# Transmitter.net
KiCad netlist of a schematic drawn in EAGLE
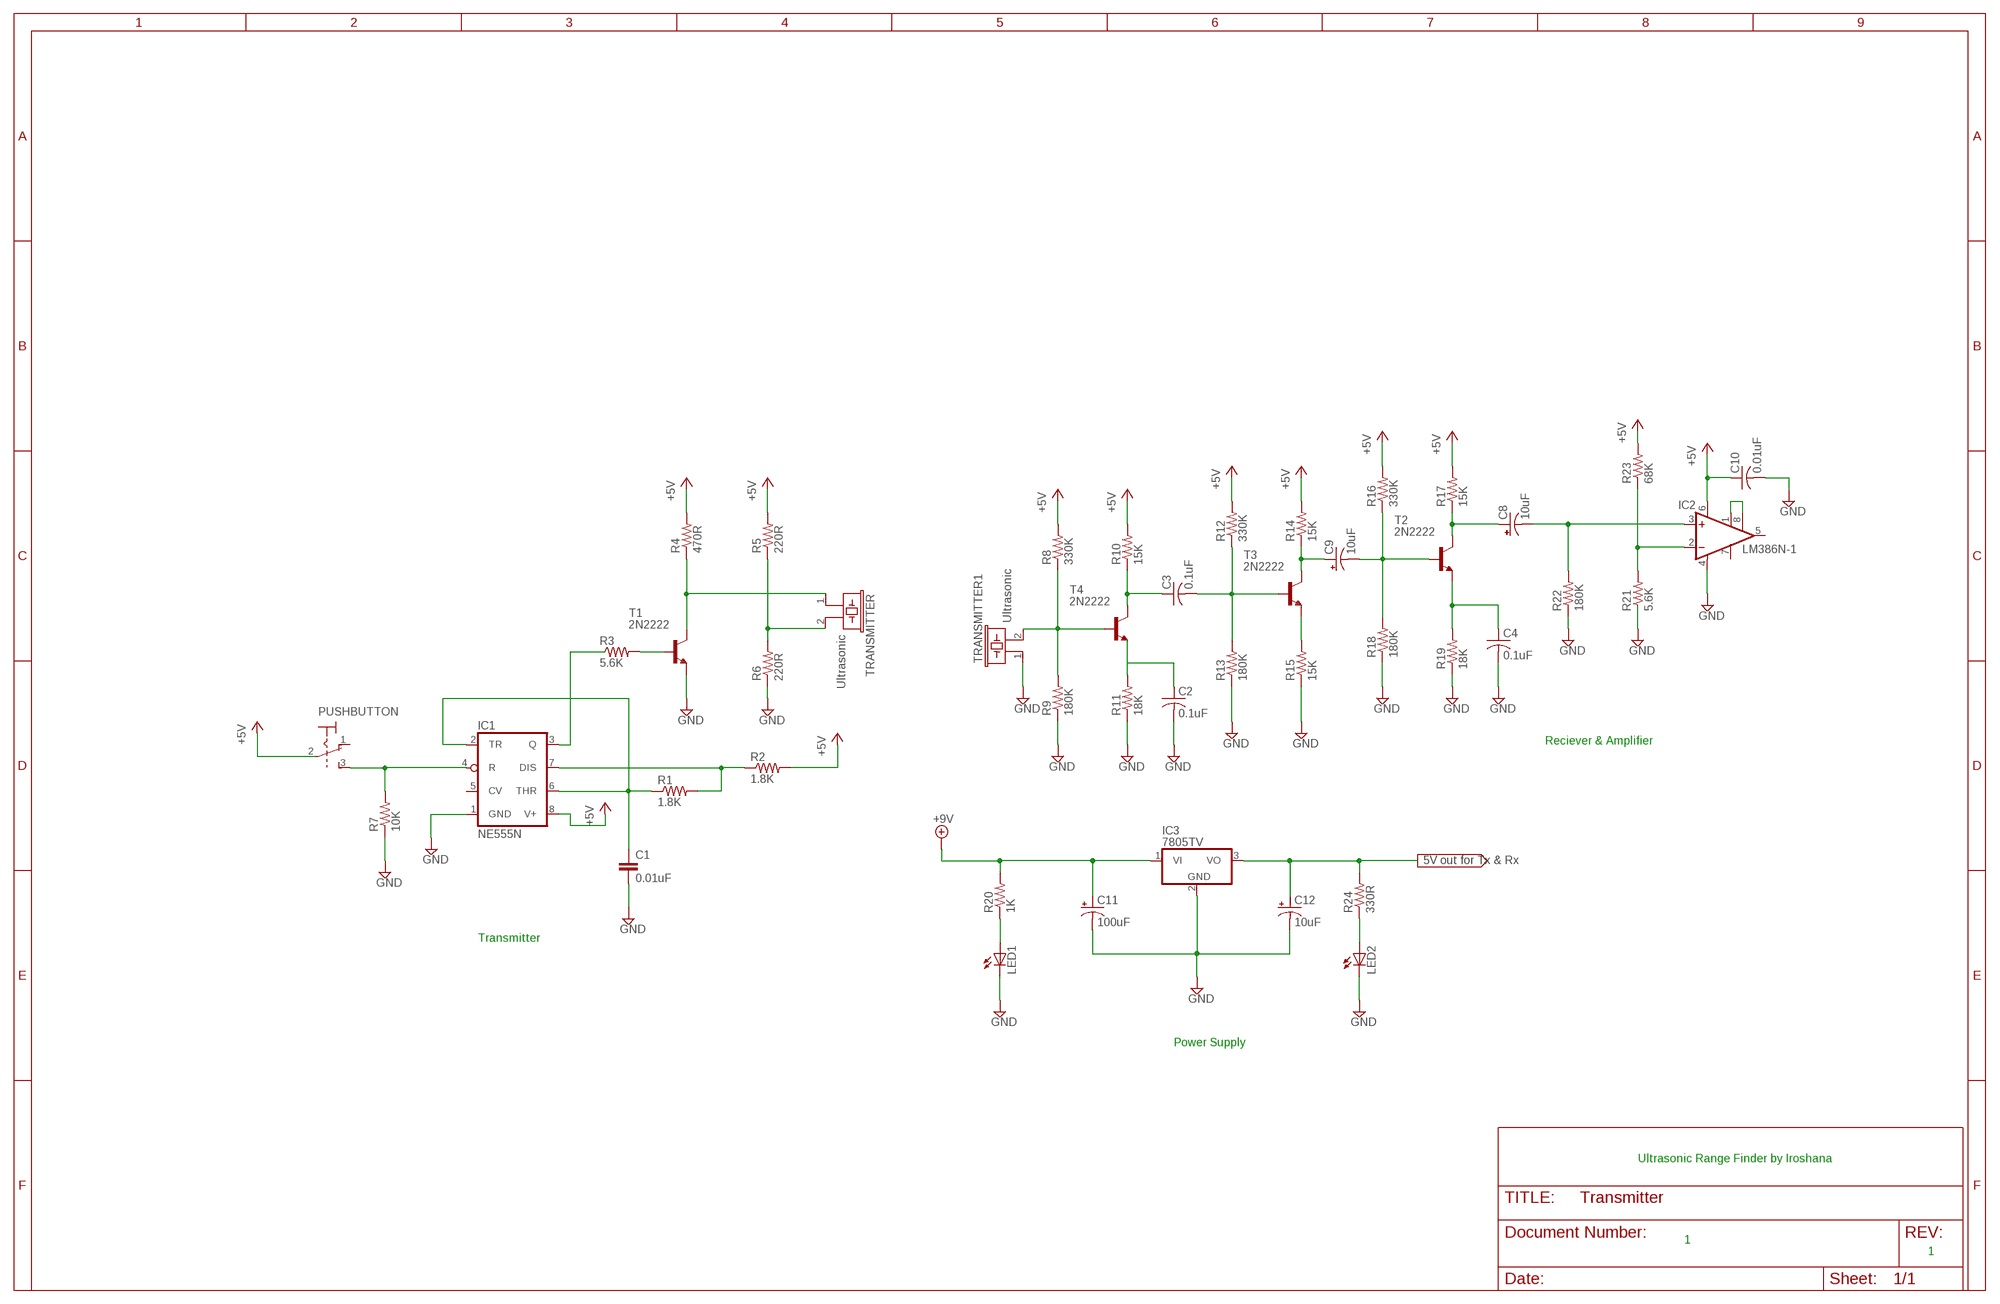
[diagram p0: schematic, sheet 1]

(export (version "E")
  (design (tool "Eeschema 10.0.6"))
  (components
    (comp (ref "C1")
      (value "0.01uF")
      (footprint "eagle-import:C2.5-2")
      (libsource (lib "eagle-import") (part "C2.5/2"))
    )
    (comp (ref "C2")
      (value "0.1uF")
      (footprint "eagle-import:C025-025X050")
      (libsource (lib "eagle-import") (part "C-US025-025X050"))
    )
    (comp (ref "C3")
      (value "0.1uF")
      (footprint "eagle-import:C025-025X050")
      (libsource (lib "eagle-import") (part "C-US025-025X050"))
    )
    (comp (ref "C4")
      (value "0.1uF")
      (footprint "eagle-import:C025-025X050")
      (libsource (lib "eagle-import") (part "C-US025-025X050"))
    )
    (comp (ref "C8")
      (value "10uF")
      (footprint "eagle-import:E2,5-6")
      (libsource (lib "eagle-import") (part "CPOL-USE2.5-6"))
    )
    (comp (ref "C9")
      (value "10uF")
      (footprint "eagle-import:E2,5-6")
      (libsource (lib "eagle-import") (part "CPOL-USE2.5-6"))
    )
    (comp (ref "C10")
      (value "0.01uF")
      (footprint "eagle-import:C025-025X050")
      (libsource (lib "eagle-import") (part "C-US025-025X050"))
    )
    (comp (ref "C11")
      (value "100uF")
      (footprint "eagle-import:E2,5-6")
      (libsource (lib "eagle-import") (part "CPOL-USE2.5-6"))
    )
    (comp (ref "C12")
      (value "10uF")
      (footprint "eagle-import:E2,5-6")
      (libsource (lib "eagle-import") (part "CPOL-USE2.5-6"))
    )
    (comp (ref "IC1")
      (value "NE555N")
      (footprint "eagle-import:DIL08-ROUND")
      (libsource (lib "eagle-import") (part "555NNE"))
    )
    (comp (ref "IC2")
      (value "LM386N-1")
      (footprint "eagle-import:DIL08")
      (libsource (lib "eagle-import") (part "LM386?-N1"))
    )
    (comp (ref "IC3")
      (value "7805TV")
      (footprint "eagle-import:TO220V")
      (libsource (lib "eagle-import") (part "78TV05"))
    )
    (comp (ref "LED1")
      (value "LED5MM")
      (footprint "eagle-import:LED5MM")
      (libsource (lib "eagle-import") (part "LED5MM"))
    )
    (comp (ref "LED2")
      (value "LED5MM")
      (footprint "eagle-import:LED5MM")
      (libsource (lib "eagle-import") (part "LED5MM"))
    )
    (comp (ref "PUSHBUTTON")
      (value "M9040P2")
      (footprint "eagle-import:M9040P2")
      (libsource (lib "eagle-import") (part "M9040P2"))
    )
    (comp (ref "R1")
      (value "1.8K")
      (footprint "eagle-import:0207_10")
      (libsource (lib "eagle-import") (part "resistor_R-US_0207/10"))
    )
    (comp (ref "R2")
      (value "1.8K")
      (footprint "eagle-import:0207_10")
      (libsource (lib "eagle-import") (part "resistor_R-US_0207/10"))
    )
    (comp (ref "R3")
      (value "5.6K")
      (footprint "eagle-import:0207_10")
      (libsource (lib "eagle-import") (part "resistor_R-US_0207/10"))
    )
    (comp (ref "R4")
      (value "470R")
      (footprint "eagle-import:0207_10")
      (libsource (lib "eagle-import") (part "resistor_R-US_0207/10"))
    )
    (comp (ref "R5")
      (value "220R")
      (footprint "eagle-import:0207_10")
      (libsource (lib "eagle-import") (part "resistor_R-US_0207/10"))
    )
    (comp (ref "R6")
      (value "220R")
      (footprint "eagle-import:0207_10")
      (libsource (lib "eagle-import") (part "resistor_R-US_0207/10"))
    )
    (comp (ref "R7")
      (value "10K")
      (footprint "eagle-import:0207_10")
      (libsource (lib "eagle-import") (part "resistor_R-US_0207/10"))
    )
    (comp (ref "R8")
      (value "330K")
      (footprint "eagle-import:0207_10")
      (libsource (lib "eagle-import") (part "R-US_0207/10"))
    )
    (comp (ref "R9")
      (value "180K")
      (footprint "eagle-import:0207_10")
      (libsource (lib "eagle-import") (part "R-US_0207/10"))
    )
    (comp (ref "R10")
      (value "15K")
      (footprint "eagle-import:0207_10")
      (libsource (lib "eagle-import") (part "R-US_0207/10"))
    )
    (comp (ref "R11")
      (value "18K")
      (footprint "eagle-import:0207_10")
      (libsource (lib "eagle-import") (part "R-US_0207/10"))
    )
    (comp (ref "R12")
      (value "330K")
      (footprint "eagle-import:0207_10")
      (libsource (lib "eagle-import") (part "R-US_0207/10"))
    )
    (comp (ref "R13")
      (value "180K")
      (footprint "eagle-import:0207_10")
      (libsource (lib "eagle-import") (part "R-US_0207/10"))
    )
    (comp (ref "R14")
      (value "15K")
      (footprint "eagle-import:0207_10")
      (libsource (lib "eagle-import") (part "R-US_0207/10"))
    )
    (comp (ref "R15")
      (value "15K")
      (footprint "eagle-import:0207_10")
      (libsource (lib "eagle-import") (part "R-US_0207/10"))
    )
    (comp (ref "R16")
      (value "330K")
      (footprint "eagle-import:0207_10")
      (libsource (lib "eagle-import") (part "R-US_0207/10"))
    )
    (comp (ref "R17")
      (value "15K")
      (footprint "eagle-import:0207_10")
      (libsource (lib "eagle-import") (part "R-US_0207/10"))
    )
    (comp (ref "R18")
      (value "180K")
      (footprint "eagle-import:0207_10")
      (libsource (lib "eagle-import") (part "R-US_0207/10"))
    )
    (comp (ref "R19")
      (value "18K")
      (footprint "eagle-import:0207_10")
      (libsource (lib "eagle-import") (part "R-US_0207/10"))
    )
    (comp (ref "R20")
      (value "1K")
      (footprint "eagle-import:0207_10")
      (libsource (lib "eagle-import") (part "R-US_0207/10"))
    )
    (comp (ref "R21")
      (value "5.6K")
      (footprint "eagle-import:0207_10")
      (libsource (lib "eagle-import") (part "R-US_0207/10"))
    )
    (comp (ref "R22")
      (value "180K")
      (footprint "eagle-import:0207_10")
      (libsource (lib "eagle-import") (part "R-US_0207/10"))
    )
    (comp (ref "R23")
      (value "68K")
      (footprint "eagle-import:0207_10")
      (libsource (lib "eagle-import") (part "R-US_0207/10"))
    )
    (comp (ref "R24")
      (value "330R")
      (footprint "eagle-import:0207_10")
      (libsource (lib "eagle-import") (part "R-US_0207/10"))
    )
    (comp (ref "T1")
      (value "2N2222")
      (footprint "eagle-import:TO92-EBC-OVAL")
      (libsource (lib "eagle-import") (part "2N2222"))
    )
    (comp (ref "T2")
      (value "2N2222")
      (footprint "eagle-import:TO92-EBC-OVAL")
      (libsource (lib "eagle-import") (part "2N2222"))
    )
    (comp (ref "T3")
      (value "2N2222")
      (footprint "eagle-import:TO92-EBC-OVAL")
      (libsource (lib "eagle-import") (part "2N2222"))
    )
    (comp (ref "T4")
      (value "2N2222")
      (footprint "eagle-import:TO92-EBC-OVAL")
      (libsource (lib "eagle-import") (part "2N2222"))
    )
    (comp (ref "TRANSMITTER")
      (value "Ultrasonic")
      (footprint "eagle-import:EFBRD22C41")
      (libsource (lib "eagle-import") (part "EFB?RD22C41"))
    )
    (comp (ref "TRANSMITTER1")
      (value "Ultrasonic")
      (footprint "eagle-import:EFBRD22C41")
      (libsource (lib "eagle-import") (part "EFB?RD22C41"))
    )
  )
  (nets
    (net (code "1") (name "+5V") (class "Default")
      (node (ref "C10") (pin "1") (pinfunction "1_1") (pintype "passive"))
      (node (ref "IC1") (pin "8") (pinfunction "V+_8") (pintype "power_in"))
      (node (ref "IC2") (pin "6") (pinfunction "VS_6") (pintype "power_in"))
      (node (ref "R10") (pin "2") (pinfunction "2_2") (pintype "passive"))
      (node (ref "R12") (pin "2") (pinfunction "2_2") (pintype "passive"))
      (node (ref "R14") (pin "2") (pinfunction "2_2") (pintype "passive"))
      (node (ref "R16") (pin "2") (pinfunction "2_2") (pintype "passive"))
      (node (ref "R17") (pin "2") (pinfunction "2_2") (pintype "passive"))
      (node (ref "R2") (pin "2") (pinfunction "2_2") (pintype "passive"))
      (node (ref "R23") (pin "2") (pinfunction "2_2") (pintype "passive"))
      (node (ref "R4") (pin "2") (pinfunction "2_2") (pintype "passive"))
      (node (ref "R5") (pin "2") (pinfunction "2_2") (pintype "passive"))
      (node (ref "R8") (pin "2") (pinfunction "2_2") (pintype "passive"))
    )
    (net (code "2") (name "+9V") (class "Default")
      (node (ref "C11") (pin "+") (pinfunction "+_+") (pintype "passive"))
      (node (ref "IC3") (pin "1") (pinfunction "VI_1") (pintype "input"))
      (node (ref "R20") (pin "2") (pinfunction "2_2") (pintype "passive"))
    )
    (net (code "3") (name "GND") (class "Default")
      (node (ref "C1") (pin "2") (pinfunction "2_2") (pintype "passive"))
      (node (ref "C10") (pin "2") (pinfunction "2_2") (pintype "passive"))
      (node (ref "C11") (pin "-") (pinfunction "-_-") (pintype "passive"))
      (node (ref "C12") (pin "-") (pinfunction "-_-") (pintype "passive"))
      (node (ref "C2") (pin "2") (pinfunction "2_2") (pintype "passive"))
      (node (ref "C4") (pin "2") (pinfunction "2_2") (pintype "passive"))
      (node (ref "IC1") (pin "1") (pinfunction "GND_1") (pintype "power_in"))
      (node (ref "IC2") (pin "4") (pinfunction "GND_4") (pintype "power_in"))
      (node (ref "IC3") (pin "2") (pinfunction "GND_2") (pintype "passive"))
      (node (ref "LED1") (pin "K") (pinfunction "C_K") (pintype "passive"))
      (node (ref "LED2") (pin "K") (pinfunction "C_K") (pintype "passive"))
      (node (ref "R11") (pin "1") (pinfunction "1_1") (pintype "passive"))
      (node (ref "R13") (pin "1") (pinfunction "1_1") (pintype "passive"))
      (node (ref "R15") (pin "1") (pinfunction "1_1") (pintype "passive"))
      (node (ref "R18") (pin "1") (pinfunction "1_1") (pintype "passive"))
      (node (ref "R19") (pin "1") (pinfunction "1_1") (pintype "passive"))
      (node (ref "R22") (pin "1") (pinfunction "1_1") (pintype "passive"))
      (node (ref "R6") (pin "1") (pinfunction "1_1") (pintype "passive"))
      (node (ref "R7") (pin "1") (pinfunction "1_1") (pintype "passive"))
      (node (ref "R9") (pin "1") (pinfunction "1_1") (pintype "passive"))
      (node (ref "T1") (pin "E") (pinfunction "E_E") (pintype "passive"))
      (node (ref "TRANSMITTER1") (pin "1") (pinfunction "1_1") (pintype "passive"))
    )
    (net (code "4") (name "Net-(C2-Pad1)") (class "Default")
      (node (ref "C2") (pin "1") (pinfunction "1_1") (pintype "passive"))
      (node (ref "R11") (pin "2") (pinfunction "2_2") (pintype "passive"))
    )
    (net (code "5") (name "Net-(C3-Pad1)") (class "Default")
      (node (ref "C3") (pin "1") (pinfunction "1_1") (pintype "passive"))
      (node (ref "R10") (pin "1") (pinfunction "1_1") (pintype "passive"))
      (node (ref "T4") (pin "C") (pinfunction "C_C") (pintype "passive"))
    )
    (net (code "6") (name "Net-(C3-Pad2)") (class "Default")
      (node (ref "C3") (pin "2") (pinfunction "2_2") (pintype "passive"))
      (node (ref "R12") (pin "1") (pinfunction "1_1") (pintype "passive"))
      (node (ref "R13") (pin "2") (pinfunction "2_2") (pintype "passive"))
      (node (ref "T3") (pin "B") (pinfunction "B_B") (pintype "passive"))
    )
    (net (code "7") (name "Net-(C4-Pad1)") (class "Default")
      (node (ref "C4") (pin "1") (pinfunction "1_1") (pintype "passive"))
      (node (ref "R19") (pin "2") (pinfunction "2_2") (pintype "passive"))
      (node (ref "T2") (pin "E") (pinfunction "E_E") (pintype "passive"))
    )
    (net (code "8") (name "Net-(C8-Pad+)") (class "Default")
      (node (ref "C8") (pin "+") (pinfunction "+_+") (pintype "passive"))
      (node (ref "R17") (pin "1") (pinfunction "1_1") (pintype "passive"))
      (node (ref "T2") (pin "C") (pinfunction "C_C") (pintype "passive"))
    )
    (net (code "9") (name "Net-(C9-Pad+)") (class "Default")
      (node (ref "C9") (pin "+") (pinfunction "+_+") (pintype "passive"))
      (node (ref "R14") (pin "1") (pinfunction "1_1") (pintype "passive"))
      (node (ref "T3") (pin "C") (pinfunction "C_C") (pintype "passive"))
    )
    (net (code "10") (name "Net-(C9-Pad-)") (class "Default")
      (node (ref "C9") (pin "-") (pinfunction "-_-") (pintype "passive"))
      (node (ref "R16") (pin "1") (pinfunction "1_1") (pintype "passive"))
      (node (ref "R18") (pin "2") (pinfunction "2_2") (pintype "passive"))
      (node (ref "T2") (pin "B") (pinfunction "B_B") (pintype "passive"))
    )
    (net (code "11") (name "Net-(IC1-DIS)") (class "Default")
      (node (ref "IC1") (pin "7") (pinfunction "DIS_7") (pintype "input"))
      (node (ref "R1") (pin "2") (pinfunction "2_2") (pintype "passive"))
      (node (ref "R2") (pin "1") (pinfunction "1_1") (pintype "passive"))
    )
    (net (code "12") (name "Net-(IC1-R)") (class "Default")
      (node (ref "IC1") (pin "4") (pinfunction "R_4") (pintype "input"))
      (node (ref "PUSHBUTTON") (pin "3") (pinfunction "S_3") (pintype "passive"))
      (node (ref "R7") (pin "2") (pinfunction "2_2") (pintype "passive"))
    )
    (net (code "13") (name "Net-(IC1-THR)") (class "Default")
      (node (ref "C1") (pin "1") (pinfunction "1_1") (pintype "passive"))
      (node (ref "IC1") (pin "2") (pinfunction "TR_2") (pintype "input"))
      (node (ref "IC1") (pin "6") (pinfunction "THR_6") (pintype "input"))
      (node (ref "R1") (pin "1") (pinfunction "1_1") (pintype "passive"))
    )
    (net (code "14") (name "Net-(IC2-+IN)") (class "Default")
      (node (ref "C8") (pin "-") (pinfunction "-_-") (pintype "passive"))
      (node (ref "IC2") (pin "3") (pinfunction "+IN_3") (pintype "input"))
      (node (ref "R22") (pin "2") (pinfunction "2_2") (pintype "passive"))
    )
    (net (code "15") (name "Net-(IC2--IN)") (class "Default")
      (node (ref "IC2") (pin "2") (pinfunction "-IN_2") (pintype "input"))
      (node (ref "R21") (pin "2") (pinfunction "2_2") (pintype "passive"))
      (node (ref "R23") (pin "1") (pinfunction "1_1") (pintype "passive"))
    )
    (net (code "16") (name "Net-(IC2-GAIN-Pad1)") (class "Default")
      (node (ref "IC2") (pin "1") (pinfunction "GAIN_1") (pintype "passive"))
      (node (ref "IC2") (pin "8") (pinfunction "GAIN_8") (pintype "passive"))
    )
    (net (code "17") (name "Net-(IC3-VO)") (class "Default")
      (node (ref "C12") (pin "+") (pinfunction "+_+") (pintype "passive"))
      (node (ref "IC3") (pin "3") (pinfunction "VO_3") (pintype "passive"))
      (node (ref "R24") (pin "2") (pinfunction "2_2") (pintype "passive"))
    )
    (net (code "18") (name "Net-(LED1-PadA)") (class "Default")
      (node (ref "LED1") (pin "A") (pinfunction "A_A") (pintype "passive"))
      (node (ref "R20") (pin "1") (pinfunction "1_1") (pintype "passive"))
    )
    (net (code "19") (name "Net-(LED2-PadA)") (class "Default")
      (node (ref "LED2") (pin "A") (pinfunction "A_A") (pintype "passive"))
      (node (ref "R24") (pin "1") (pinfunction "1_1") (pintype "passive"))
    )
    (net (code "20") (name "Net-(R3-Pad2)") (class "Default")
      (node (ref "R3") (pin "2") (pinfunction "2_2") (pintype "passive"))
      (node (ref "T1") (pin "B") (pinfunction "B_B") (pintype "passive"))
    )
    (net (code "21") (name "Net-(R4-Pad1)") (class "Default")
      (node (ref "R4") (pin "1") (pinfunction "1_1") (pintype "passive"))
      (node (ref "T1") (pin "C") (pinfunction "C_C") (pintype "passive"))
      (node (ref "TRANSMITTER") (pin "1") (pinfunction "1_1") (pintype "passive"))
    )
    (net (code "22") (name "Net-(R5-Pad1)") (class "Default")
      (node (ref "R5") (pin "1") (pinfunction "1_1") (pintype "passive"))
      (node (ref "R6") (pin "2") (pinfunction "2_2") (pintype "passive"))
      (node (ref "TRANSMITTER") (pin "2") (pinfunction "2_2") (pintype "passive"))
    )
    (net (code "23") (name "Net-(R8-Pad1)") (class "Default")
      (node (ref "R8") (pin "1") (pinfunction "1_1") (pintype "passive"))
      (node (ref "R9") (pin "2") (pinfunction "2_2") (pintype "passive"))
      (node (ref "T4") (pin "B") (pinfunction "B_B") (pintype "passive"))
      (node (ref "TRANSMITTER1") (pin "2") (pinfunction "2_2") (pintype "passive"))
    )
    (net (code "24") (name "Net-(R15-Pad2)") (class "Default")
      (node (ref "R15") (pin "2") (pinfunction "2_2") (pintype "passive"))
      (node (ref "T3") (pin "E") (pinfunction "E_E") (pintype "passive"))
    )
    (net (code "25") (name "unconnected-(IC1-CV-Pad5)") (class "Default")
      (node (ref "IC1") (pin "5") (pinfunction "CV_5") (pintype "input"))
    )
    (net (code "26") (name "unconnected-(IC1-Q-Pad3)") (class "Default")
      (node (ref "IC1") (pin "3") (pinfunction "Q_3") (pintype "output"))
    )
    (net (code "27") (name "unconnected-(IC2-BYPASS-Pad7)") (class "Default")
      (node (ref "IC2") (pin "7") (pinfunction "BYPASS_7") (pintype "passive"))
    )
    (net (code "28") (name "unconnected-(IC2-OUT-Pad5)") (class "Default")
      (node (ref "IC2") (pin "5") (pinfunction "OUT_5") (pintype "output"))
    )
    (net (code "29") (name "unconnected-(PUSHBUTTONA-O-Pad1)") (class "Default")
      (node (ref "PUSHBUTTON") (pin "1") (pinfunction "O_1") (pintype "passive"))
    )
    (net (code "30") (name "unconnected-(PUSHBUTTONA-P-Pad2)") (class "Default")
      (node (ref "PUSHBUTTON") (pin "2") (pinfunction "P_2") (pintype "passive"))
    )
    (net (code "31") (name "unconnected-(R3-Pad1)") (class "Default")
      (node (ref "R3") (pin "1") (pinfunction "1_1") (pintype "passive"))
    )
    (net (code "32") (name "unconnected-(R21-Pad1)") (class "Default")
      (node (ref "R21") (pin "1") (pinfunction "1_1") (pintype "passive"))
    )
    (net (code "33") (name "unconnected-(T4-PadE)") (class "Default")
      (node (ref "T4") (pin "E") (pinfunction "E_E") (pintype "passive"))
    )
  )
)
